# DenScript_Pixel_v1_1.net
KiCad netlist of a schematic drawn in EAGLE
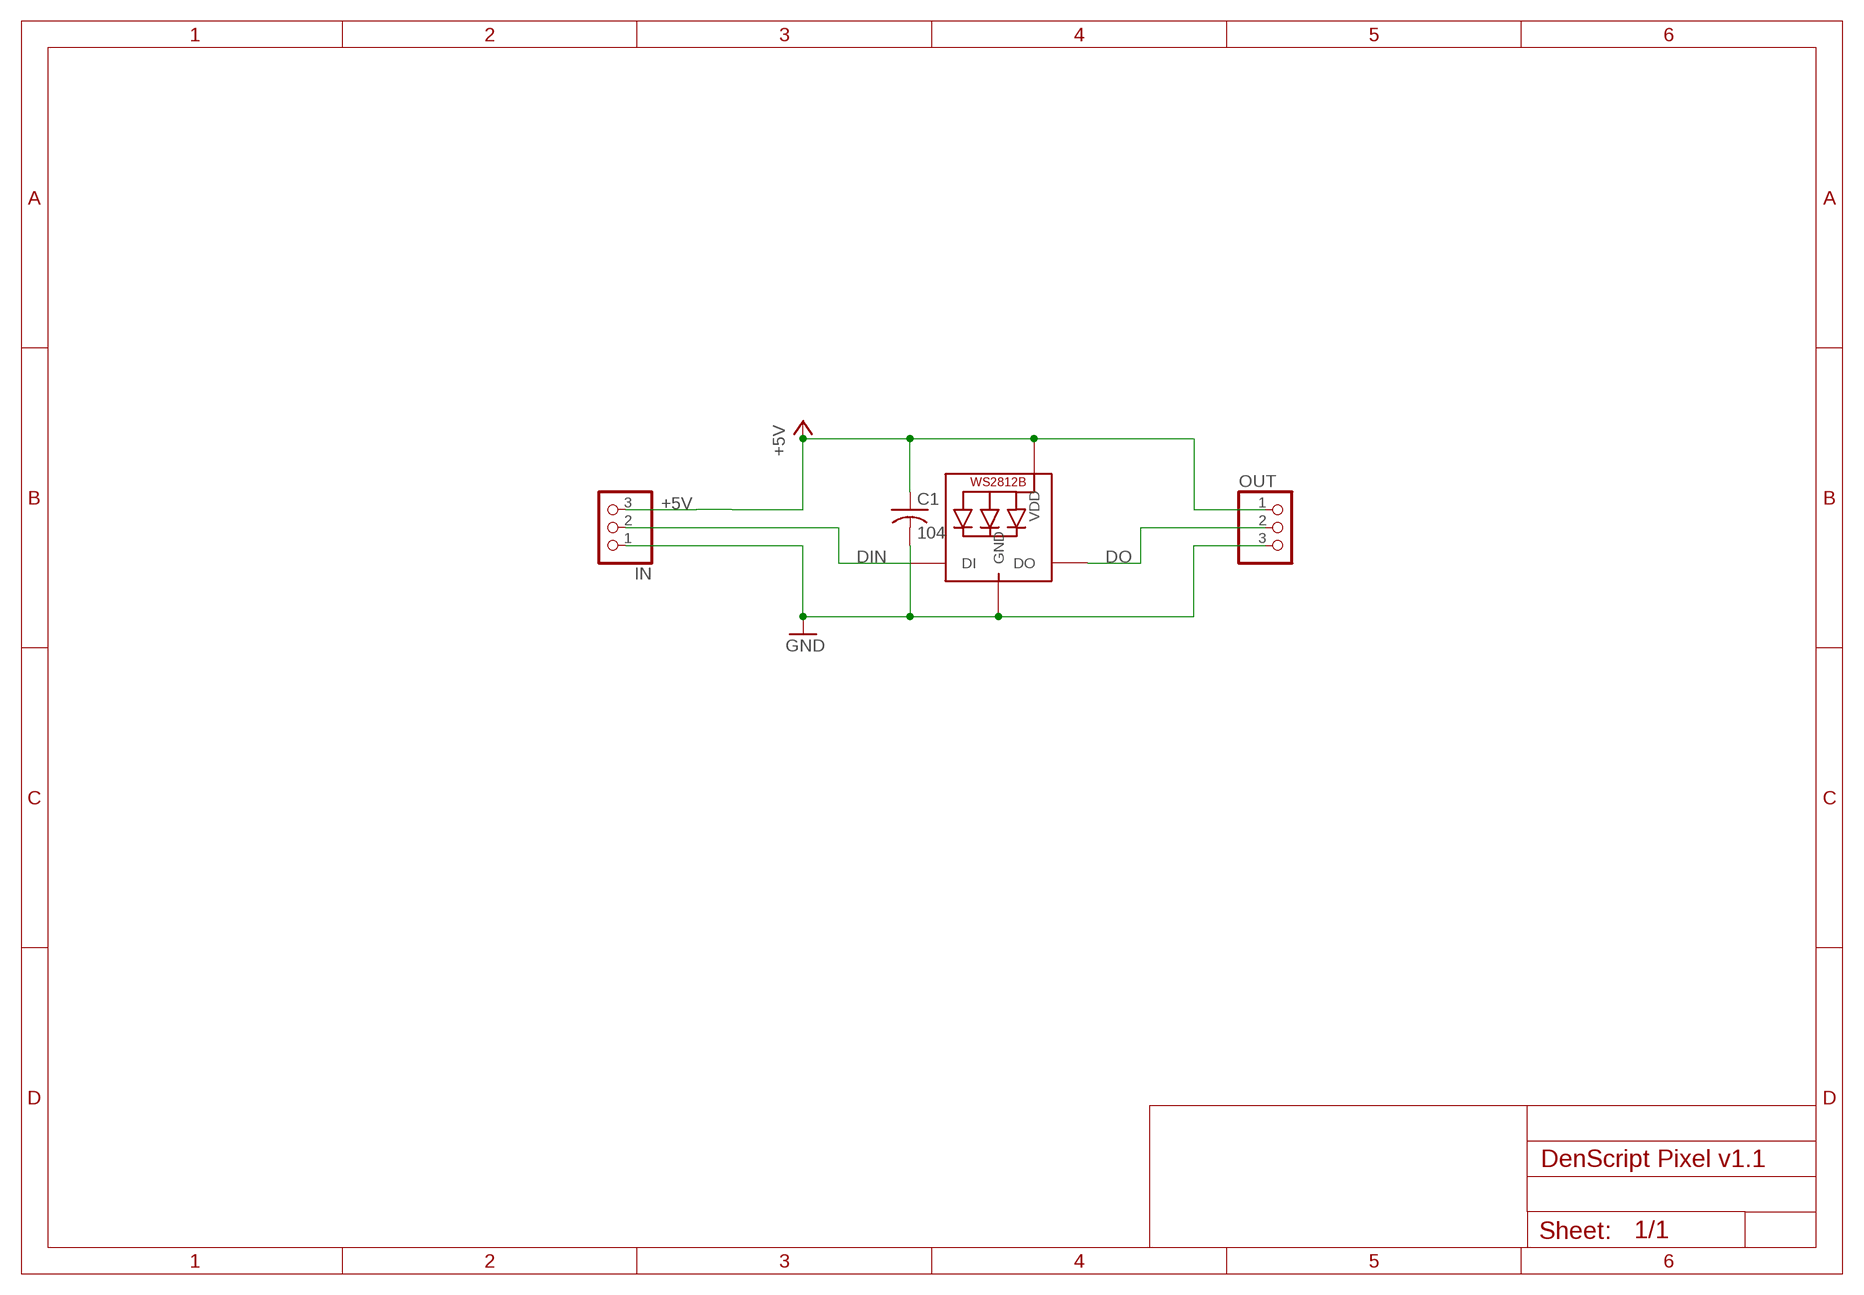
[diagram p0: schematic, sheet 1]

(export (version "E")
  (design (tool "Eeschema 10.0.6"))
  (components
    (comp (ref "C1")
      (value "104")
      (footprint "eagle-import:C0603K")
      (libsource (lib "eagle-import") (part "C-USC0603K"))
    )
    (comp (ref "IN")
      (value "PINHD-1X3")
      (footprint "eagle-import:1X03")
      (libsource (lib "eagle-import") (part "PINHD-1X3"))
    )
    (comp (ref "LED1")
      (value "WS2812B_5050N")
      (footprint "eagle-import:WS2812B-NARROW")
      (libsource (lib "eagle-import") (part "WS2812B_5050N"))
    )
    (comp (ref "OUT")
      (value "PINHD-1X3")
      (footprint "eagle-import:1X03")
      (libsource (lib "eagle-import") (part "PINHD-1X3"))
    )
  )
  (nets
    (net (code "1") (name "+5V") (class "Default")
      (node (ref "C1") (pin "1") (pinfunction "1_1") (pintype "passive"))
      (node (ref "IN") (pin "3") (pinfunction "3_3") (pintype "passive"))
      (node (ref "LED1") (pin "1-VDD") (pinfunction "VDD_1-VDD") (pintype "power_in"))
      (node (ref "OUT") (pin "1") (pinfunction "1_1") (pintype "passive"))
    )
    (net (code "2") (name "/DIN") (class "Default")
      (node (ref "IN") (pin "2") (pinfunction "2_2") (pintype "passive"))
      (node (ref "LED1") (pin "4-DIN") (pinfunction "DI_4-DIN") (pintype "input"))
    )
    (net (code "3") (name "/DO") (class "Default")
      (node (ref "LED1") (pin "2-DOUT") (pinfunction "DO_2-DOUT") (pintype "output"))
      (node (ref "OUT") (pin "2") (pinfunction "2_2") (pintype "passive"))
    )
    (net (code "4") (name "GND") (class "Default")
      (node (ref "C1") (pin "2") (pinfunction "2_2") (pintype "passive"))
      (node (ref "IN") (pin "1") (pinfunction "1_1") (pintype "passive"))
      (node (ref "LED1") (pin "3-GND") (pinfunction "GND_3-GND") (pintype "power_in"))
      (node (ref "OUT") (pin "3") (pinfunction "3_3") (pintype "passive"))
    )
  )
)
